# Page-8.net
KiCad netlist of a schematic drawn in Altium Designer
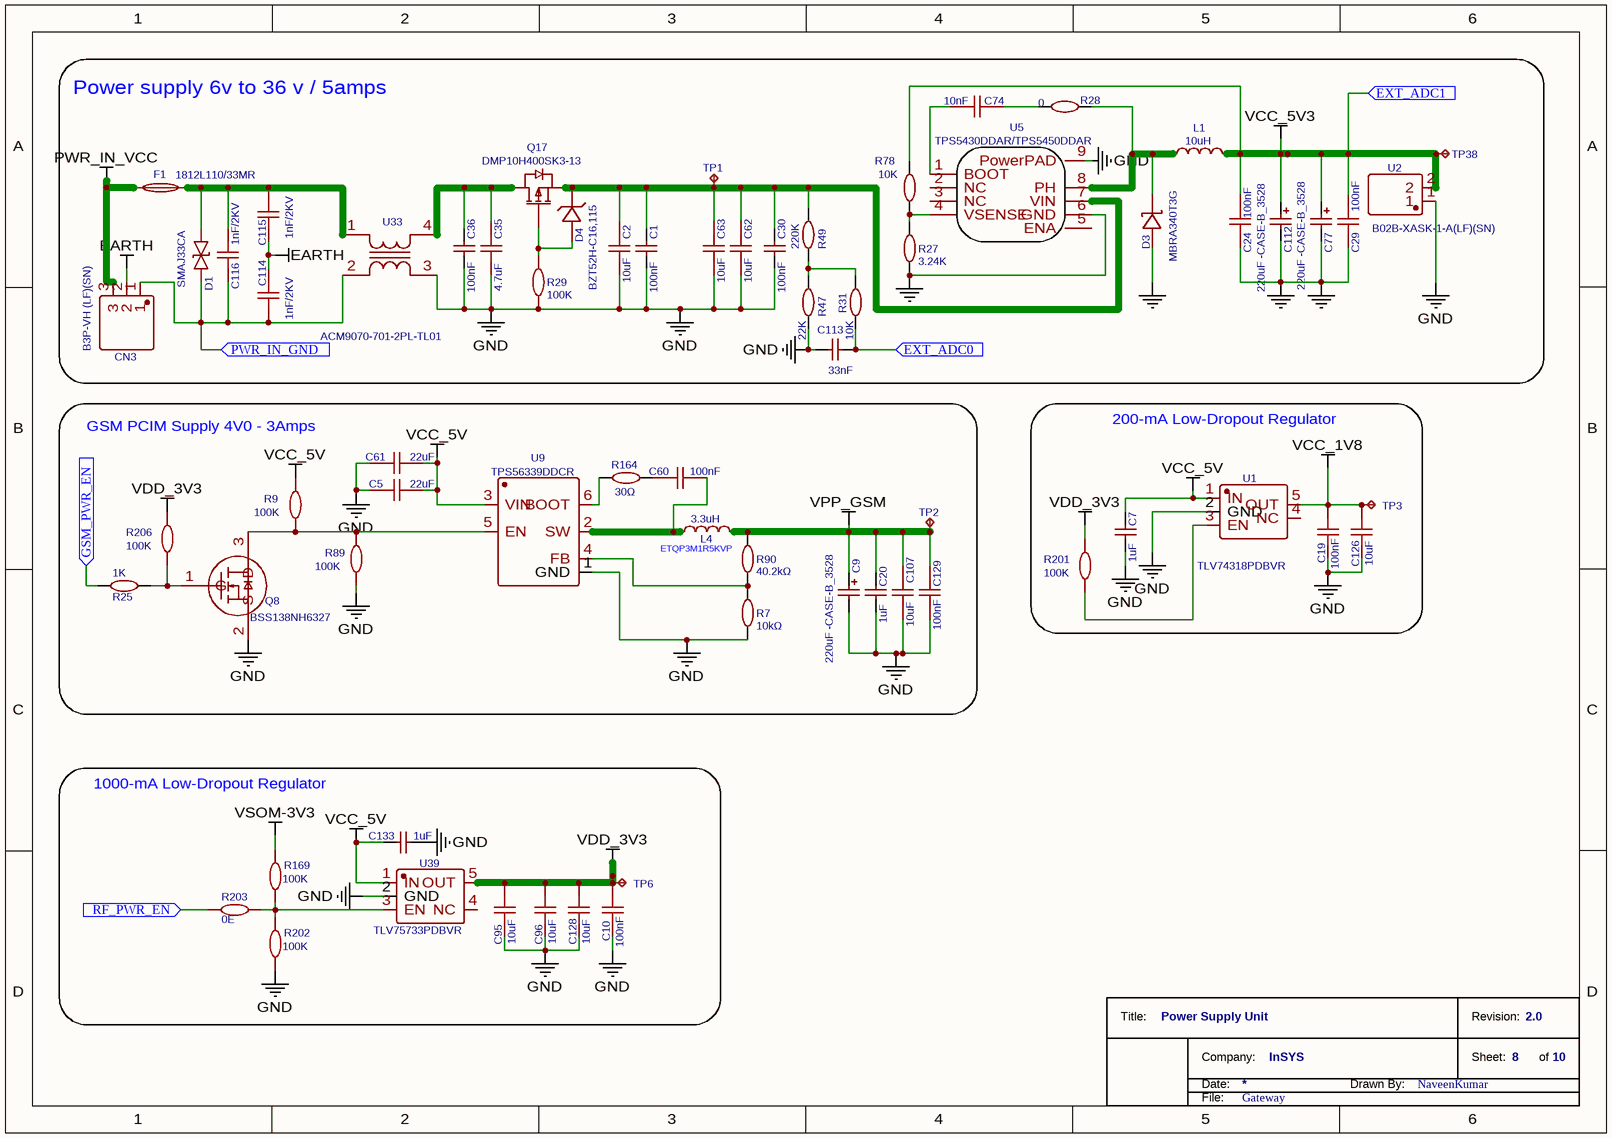
[diagram p0: Page-8.schdoc]

(export (version "E")
  (design (tool "Eeschema 10.0.6"))
  (components
    (comp (ref "*")
      (value "TitleBlock_1")
      (description "TitleBlock  No-2")
      (fields (field (name "DRAWN BY") "*"))
      (libsource (lib "GateWay_AllwinnerV2") (part "TitleBlock_1"))
    )
    (comp (ref "C1")
      (value "100nF")
      (footprint "GWAY_Capacitor_0805")
      (fields
        (field (name "MANUFACTURER PART") "CL21B104KCFNNNE")
        (field (name "MANUFACTURER") "SAMSUNG(三星)")
      )
      (libsource (lib "altium-import") (part "root_1_100nF_"))
    )
    (comp (ref "C2")
      (value "10uF")
      (footprint "GWAY_Capacitor_1206")
      (fields
        (field (name "MANUFACTURER") "SAMSUNG(三星)")
        (field (name "MANUFACTURER PART") "CL31B106KBHNNNE")
      )
      (libsource (lib "altium-import") (part "root_1_10uF_"))
    )
    (comp (ref "C5")
      (value "22uF")
      (footprint "GWAY_Capacitor_0805")
      (fields (field (name "MANUFACTURER") "SAMSUNG") (field (name "MANUFACTURER PART") "CL21A226MQQNNNE"))
      (libsource (lib "altium-import") (part "root_2_22uF_"))
    )
    (comp (ref "C7")
      (value "1uF")
      (footprint "GWAY_Capacitor_0603")
      (fields
        (field (name "MANUFACTURER PART") "CL10B105KA8NNNC")
        (field (name "MANUFACTURER") "SAMSUNG(三星)")
      )
      (libsource (lib "altium-import") (part "root_3_1uF_"))
    )
    (comp (ref "C9")
      (value "220uF -CASE-B_3528")
      (footprint "GWAY_CASE-B")
      (fields (field (name "MANUFACTURER") "PANASONIC") (field (name "MANUFACTURER PART") "6TPE220MAZB"))
      (libsource (lib "altium-import") (part "root_3_220uF -CASE-B_3528_"))
    )
    (comp (ref "C10")
      (value "100nF")
      (footprint "GWAY_Capacitor_0603")
      (fields (field (name "MANUFACTURER") "SAMSUNG") (field (name "MANUFACTURER PART") "CL10B104KB8NNNC"))
      (libsource (lib "") (part "root_1_100nF__1"))
    )
    (comp (ref "C19")
      (value "100nF")
      (footprint "GWAY_Capacitor_0603")
      (fields (field (name "MANUFACTURER") "SAMSUNG") (field (name "MANUFACTURER PART") "CL10B104KB8NNNC"))
      (libsource (lib "") (part "root_1_100nF__1"))
    )
    (comp (ref "C20")
      (value "1uF")
      (footprint "GWAY_Capacitor_0603")
      (fields
        (field (name "MANUFACTURER PART") "CL10B105KA8NNNC")
        (field (name "MANUFACTURER") "SAMSUNG(三星)")
      )
      (libsource (lib "altium-import") (part "root_3_1uF_"))
    )
    (comp (ref "C24")
      (value "100nF")
      (footprint "GWAY_Capacitor_0603")
      (fields (field (name "MANUFACTURER") "SAMSUNG") (field (name "MANUFACTURER PART") "CL10B104KB8NNNC"))
      (libsource (lib "altium-import") (part "root_3_100nF_"))
    )
    (comp (ref "C29")
      (value "100nF")
      (footprint "GWAY_Capacitor_0603")
      (fields (field (name "MANUFACTURER") "SAMSUNG") (field (name "MANUFACTURER PART") "CL10B104KB8NNNC"))
      (libsource (lib "altium-import") (part "root_3_100nF_"))
    )
    (comp (ref "C30")
      (value "100nF")
      (footprint "GWAY_Capacitor_0805")
      (fields
        (field (name "MANUFACTURER PART") "CL21B104KCFNNNE")
        (field (name "MANUFACTURER") "SAMSUNG(三星)")
      )
      (libsource (lib "altium-import") (part "root_1_100nF_"))
    )
    (comp (ref "C35")
      (value "4.7uF")
      (footprint "GWAY_CAP1210")
      (fields
        (field (name "MANUFACTURER") "TAIYO YUDEN(太诱)")
        (field (name "MANUFACTURER PART") "HMK325C7475KN-TE")
        (field (name "CONTRIBUTOR") "LCSC")
      )
      (libsource (lib "altium-import") (part "root_1_4.7uF_"))
    )
    (comp (ref "C36")
      (value "100nF")
      (footprint "GWAY_Capacitor_0805")
      (fields
        (field (name "MANUFACTURER PART") "CL21B104KCFNNNE")
        (field (name "MANUFACTURER") "SAMSUNG(三星)")
      )
      (libsource (lib "altium-import") (part "root_1_100nF_"))
    )
    (comp (ref "C60")
      (value "100nF")
      (footprint "GWAY_Capacitor_0603")
      (fields (field (name "MANUFACTURER") "SAMSUNG") (field (name "MANUFACTURER PART") "CL10B104KB8NNNC"))
      (libsource (lib "altium-import") (part "root_2_100nF_"))
    )
    (comp (ref "C61")
      (value "22uF")
      (footprint "GWAY_Capacitor_0805")
      (fields (field (name "MANUFACTURER") "SAMSUNG") (field (name "MANUFACTURER PART") "CL21A226MQQNNNE"))
      (libsource (lib "altium-import") (part "root_2_22uF_"))
    )
    (comp (ref "C62")
      (value "10uF")
      (footprint "GWAY_Capacitor_1206")
      (fields
        (field (name "MANUFACTURER") "SAMSUNG(三星)")
        (field (name "MANUFACTURER PART") "CL31B106KBHNNNE")
      )
      (libsource (lib "altium-import") (part "root_1_10uF_"))
    )
    (comp (ref "C63")
      (value "10uF")
      (footprint "GWAY_Capacitor_1206")
      (fields
        (field (name "MANUFACTURER") "SAMSUNG(三星)")
        (field (name "MANUFACTURER PART") "CL31B106KBHNNNE")
      )
      (libsource (lib "altium-import") (part "root_1_10uF_"))
    )
    (comp (ref "C74")
      (value "10nF")
      (footprint "GWAY_Capacitor_0603")
      (fields
        (field (name "MANUFACTURER") "Samsung Electro-Mechanics")
        (field (name "MANUFACTURER PART") "CL10B103KB8NFNC")
        (field (name "CONTRIBUTOR") "LCSC")
      )
      (libsource (lib "altium-import") (part "root_1_10nF_"))
    )
    (comp (ref "C77")
      (value "220uF -CASE-B_3528")
      (footprint "GWAY_CASE-B")
      (fields (field (name "MANUFACTURER") "PANASONIC") (field (name "MANUFACTURER PART") "6TPE220MAZB"))
      (libsource (lib "altium-import") (part "root_3_220uF -CASE-B_3528_"))
    )
    (comp (ref "C95")
      (value "10uF")
      (footprint "GWAY_Capacitor_0805")
      (fields
        (field (name "MANUFACTURER") "SAMSUNG(三星)")
        (field (name "MANUFACTURER PART") "CL21B106KOQNNNE")
      )
      (libsource (lib "altium-import") (part "root_1_10uF_"))
    )
    (comp (ref "C96")
      (value "10uF")
      (footprint "GWAY_Capacitor_0805")
      (fields
        (field (name "MANUFACTURER") "SAMSUNG(三星)")
        (field (name "MANUFACTURER PART") "CL21B106KOQNNNE")
      )
      (libsource (lib "altium-import") (part "root_1_10uF_"))
    )
    (comp (ref "C107")
      (value "10uF")
      (footprint "GWAY_Capacitor_0805")
      (fields
        (field (name "MANUFACTURER") "SAMSUNG(三星)")
        (field (name "MANUFACTURER PART") "CL21B106KOQNNNE")
      )
      (libsource (lib "altium-import") (part "root_1_10uF_"))
    )
    (comp (ref "C112")
      (value "220uF -CASE-B_3528")
      (footprint "GWAY_CASE-B")
      (fields (field (name "MANUFACTURER") "PANASONIC") (field (name "MANUFACTURER PART") "6TPE220MAZB"))
      (libsource (lib "altium-import") (part "root_3_220uF -CASE-B_3528_"))
    )
    (comp (ref "C113")
      (value "33nF")
      (footprint "GWAY_Capacitor_0603")
      (fields (field (name "MANUFACTURER PART") "CL10B333KB8NNNC") (field (name "MANUFACTURER") "SAMSUNG"))
      (libsource (lib "altium-import") (part "root_2_33nF_"))
    )
    (comp (ref "C114")
      (value "1nF/2KV")
      (footprint "GWAY_Capacitor_1206")
      (fields
        (field (name "MANUFACTURER") "Walsin Tech Corp")
        (field (name "MANUFACTURER PART") "1206B102K202CT")
        (field (name "CONTRIBUTOR") "LCSC")
      )
      (libsource (lib "altium-import") (part "root_1_1nF/2KV_"))
    )
    (comp (ref "C115")
      (value "1nF/2KV")
      (footprint "GWAY_Capacitor_1206")
      (fields
        (field (name "MANUFACTURER") "Walsin Tech Corp")
        (field (name "MANUFACTURER PART") "1206B102K202CT")
        (field (name "CONTRIBUTOR") "LCSC")
      )
      (libsource (lib "altium-import") (part "root_1_1nF/2KV_"))
    )
    (comp (ref "C116")
      (value "1nF/2KV")
      (footprint "GWAY_Capacitor_1206")
      (fields
        (field (name "MANUFACTURER") "Walsin Tech Corp")
        (field (name "MANUFACTURER PART") "1206B102K202CT")
        (field (name "CONTRIBUTOR") "LCSC")
      )
      (libsource (lib "altium-import") (part "root_1_1nF/2KV_"))
    )
    (comp (ref "C126")
      (value "10uF")
      (footprint "GWAY_Capacitor_0805")
      (fields
        (field (name "MANUFACTURER") "SAMSUNG(三星)")
        (field (name "MANUFACTURER PART") "CL21B106KOQNNNE")
      )
      (libsource (lib "altium-import") (part "root_1_10uF_"))
    )
    (comp (ref "C128")
      (value "10uF")
      (footprint "GWAY_Capacitor_0805")
      (fields
        (field (name "MANUFACTURER") "SAMSUNG(三星)")
        (field (name "MANUFACTURER PART") "CL21B106KOQNNNE")
      )
      (libsource (lib "altium-import") (part "root_1_10uF_"))
    )
    (comp (ref "C129")
      (value "100nF")
      (footprint "GWAY_Capacitor_0603")
      (fields (field (name "MANUFACTURER") "SAMSUNG") (field (name "MANUFACTURER PART") "CL10B104KB8NNNC"))
      (libsource (lib "") (part "root_1_100nF__1"))
    )
    (comp (ref "C133")
      (value "1uF")
      (footprint "GWAY_Capacitor_0603")
      (fields
        (field (name "MANUFACTURER PART") "CL10B105KA8NNNC")
        (field (name "MANUFACTURER") "SAMSUNG(三星)")
      )
      (libsource (lib "altium-import") (part "root_0_1uF_"))
    )
    (comp (ref "CN3")
      (value "B3P-VH (LF)(SN)")
      (footprint "GWAY_B3P-VH-LF-SN")
      (fields (field (name "MANUFACTURER") "JST Sales America") (field (name "CONTRIBUTOR") "LCSC"))
      (libsource (lib "altium-import") (part "root_3_B3P-VH (LF)(SN)_"))
    )
    (comp (ref "D1")
      (value "SMAJ33CA")
      (footprint "GWAY_Diode_SMA_DO214AC")
      (fields (field (name "MANUFACTURER") "Littelfuse") (field (name "CONTRIBUTOR") "LCSC"))
      (libsource (lib "altium-import") (part "root_1_SMAJ33CA_"))
    )
    (comp (ref "D3")
      (value "MBRA340T3G")
      (footprint "GWAY_Diode_SMA_DO214AC")
      (fields (field (name "MANUFACTURER") "ON"))
      (libsource (lib "altium-import") (part "root_1_MBRA340T3G_"))
    )
    (comp (ref "D4")
      (value "BZT52H-C16,115")
      (footprint "GWAY_SOD123F")
      (fields (field (name "MANUFACTURER") "Nexperia(安世)") (field (name "CONTRIBUTOR") "LCSC"))
      (libsource (lib "altium-import") (part "root_3_BZT52H-C16,115_"))
    )
    (comp (ref "F1")
      (value "1812L110/33MR")
      (footprint "GWAY_FUSE1812L110/33MR")
      (fields (field (name "MANUFACTURER") "Littelfuse") (field (name "CONTRIBUTOR") "LCSC"))
      (libsource (lib "altium-import") (part "root_0_1812L110/33MR_"))
    )
    (comp (ref "L1")
      (value "10uH")
      (footprint "GWAY_ETQP5M100YFC")
      (fields
        (field (name "MANUFACTURER") "PANASONIC")
        (field (name "MANUFACTURER PART") "ETQP5M100YFC")
        (field (name "CONTRIBUTOR") "LCSC")
      )
      (libsource (lib "altium-import") (part "root_0_10uH_"))
    )
    (comp (ref "L4")
      (value "3.3uH")
      (footprint "GWAY_ETQ-P3M_KVP")
      (fields (field (name "MANUFACTURER PART") "TDK") (field (name "MANUFACTURER") "ETQP3M3R3KVP"))
      (libsource (lib "altium-import") (part "root_0_3.3uH_"))
    )
    (comp (ref "Q8")
      (value "BSS138NH6327")
      (footprint "GWAY_SOT23-3PIN")
      (fields (field (name "MANUFACTURER") "Infineon(英飞凌)") (field (name "CONTRIBUTOR") "LCSC"))
      (libsource (lib "GateWay_AllwinnerV2") (part "BSS138NH6327"))
    )
    (comp (ref "Q17")
      (value "DMP10H400SK3-13")
      (footprint "GWAY_P-CH MOSFET_DMP10H400SK313")
      (fields (field (name "MANUFACTURER") "DIODES(美台)") (field (name "CONTRIBUTOR") "LCSC"))
      (libsource (lib "altium-import") (part "root_1_DMP10H400SK3-13_"))
    )
    (comp (ref "R7")
      (value "10kΩ")
      (footprint "GWAY_Resistor_0603")
      (fields (field (name "MANUFACTURER") "YAGEO(国巨)"))
      (libsource (lib "altium-import") (part "root_1_10kΩ_"))
    )
    (comp (ref "R9")
      (value "100K")
      (footprint "GWAY_Resistor_0603")
      (fields
        (field (name "MANUFACTURER") "YAGEO")
        (field (name "MANUFACTURER PART") "RC0603FR-07100KL")
        (field (name "CONTRIBUTOR") "LCSC")
      )
      (libsource (lib "altium-import") (part "root_1_100K_"))
    )
    (comp (ref "R25")
      (value "1K")
      (footprint "GWAY_Resistor_0603")
      (fields (field (name "MANUFACTURER PART") "RC0603FR-071KL") (field (name "MANUFACTURER") "YAGEO"))
      (libsource (lib "altium-import") (part "root_2_1K_"))
    )
    (comp (ref "R27")
      (value "3.24K")
      (footprint "GWAY_Resistor_0603")
      (fields (field (name "MANUFACTURER") "YAGEO") (field (name "MANUFACTURER PART") "RC0603FR-073KL"))
      (libsource (lib "altium-import") (part "root_1_3.24K_"))
    )
    (comp (ref "R28")
      (value "0")
      (footprint "GWAY_Resistor_0603")
      (fields (field (name "MANUFACTURER") "YAGEO") (field (name "MANUFACTURER PART") "RC0603FR-070RL"))
      (libsource (lib "altium-import") (part "root_0_0_"))
    )
    (comp (ref "R29")
      (value "100K")
      (footprint "GWAY_Resistor_0603")
      (fields
        (field (name "MANUFACTURER") "YAGEO")
        (field (name "MANUFACTURER PART") "RC0603FR-07100KL")
        (field (name "CONTRIBUTOR") "LCSC")
      )
      (libsource (lib "altium-import") (part "root_1_100K_"))
    )
    (comp (ref "R31")
      (value "10K")
      (footprint "GWAY_Resistor_0603")
      (fields (field (name "MANUFACTURER") "YAGEO") (field (name "MANUFACTURER PART") "RC0603JR-0710KL"))
      (libsource (lib "altium-import") (part "root_3_10K_"))
    )
    (comp (ref "R47")
      (value "22K")
      (footprint "GWAY_Resistor_0805")
      (fields (field (name "MANUFACTURER") "YAGEO") (field (name "MANUFACTURER PART") "RC0805JR-0722KL"))
      (libsource (lib "altium-import") (part "root_1_22K_"))
    )
    (comp (ref "R49")
      (value "220K")
      (footprint "GWAY_Resistor_0805")
      (fields (field (name "MANUFACTURER") "YAGEO") (field (name "MANUFACTURER PART") "RC0805FR-07220KL"))
      (libsource (lib "altium-import") (part "root_1_220K_"))
    )
    (comp (ref "R78")
      (value "10K")
      (footprint "GWAY_Resistor_0603")
      (fields (field (name "MANUFACTURER") "YAGEO") (field (name "MANUFACTURER PART") "RC0603JR-0710KL"))
      (libsource (lib "altium-import") (part "root_3_10K_"))
    )
    (comp (ref "R89")
      (value "100K")
      (footprint "GWAY_Resistor_0603")
      (fields
        (field (name "MANUFACTURER") "YAGEO")
        (field (name "MANUFACTURER PART") "RC0603FR-07100KL")
        (field (name "CONTRIBUTOR") "LCSC")
      )
      (libsource (lib "altium-import") (part "root_1_100K_"))
    )
    (comp (ref "R90")
      (value "40.2kΩ")
      (footprint "GWAY_Resistor_0603")
      (fields (field (name "MANUFACTURER") "YAGEO(国巨)"))
      (libsource (lib "altium-import") (part "root_1_40.2kΩ_"))
    )
    (comp (ref "R164")
      (value "30Ω")
      (footprint "GWAY_Resistor_0603")
      (fields (field (name "MANUFACTURER") "YAGEO(国巨)"))
      (libsource (lib "altium-import") (part "root_0_30Ω_"))
    )
    (comp (ref "R169")
      (value "100K")
      (footprint "GWAY_Resistor_0603")
      (fields
        (field (name "MANUFACTURER") "YAGEO")
        (field (name "MANUFACTURER PART") "RC0603FR-07100KL")
        (field (name "CONTRIBUTOR") "LCSC")
      )
      (libsource (lib "altium-import") (part "root_1_100K_"))
    )
    (comp (ref "R201")
      (value "100K")
      (footprint "GWAY_Resistor_0603")
      (fields
        (field (name "MANUFACTURER") "YAGEO")
        (field (name "MANUFACTURER PART") "RC0603FR-07100KL")
        (field (name "CONTRIBUTOR") "LCSC")
      )
      (libsource (lib "altium-import") (part "root_1_100K_"))
    )
    (comp (ref "R202")
      (value "100K")
      (footprint "GWAY_Resistor_0603")
      (fields
        (field (name "MANUFACTURER") "YAGEO")
        (field (name "MANUFACTURER PART") "RC0603FR-07100KL")
        (field (name "CONTRIBUTOR") "LCSC")
      )
      (libsource (lib "altium-import") (part "root_1_100K_"))
    )
    (comp (ref "R203")
      (value "0E")
      (footprint "GWAY_Resistor_0603")
      (fields
        (field (name "MANUFACTURER") "YAGEO")
        (field (name "MANUFACTURER PART") "RC0603FR-07100KL")
        (field (name "CONTRIBUTOR") "LCSC")
      )
      (libsource (lib "altium-import") (part "root_2_100K_"))
    )
    (comp (ref "R206")
      (value "100K")
      (footprint "GWAY_Resistor_0603")
      (fields
        (field (name "MANUFACTURER") "YAGEO")
        (field (name "MANUFACTURER PART") "RC0603FR-07100KL")
        (field (name "CONTRIBUTOR") "LCSC")
      )
      (libsource (lib "altium-import") (part "root_1_100K_"))
    )
    (comp (ref "TP1")
      (value "TP-052-TJ")
      (footprint "GWAY_TESTPOINT1")
      (fields (field (name "MANUFACTURER PART") "?"))
      (libsource (lib "altium-import") (part "root_0_TP-052-TJ_"))
    )
    (comp (ref "TP2")
      (value "TP-052-TJ")
      (footprint "GWAY_TESTPOINT1")
      (fields (field (name "MANUFACTURER PART") "?"))
      (libsource (lib "altium-import") (part "root_0_TP-052-TJ_"))
    )
    (comp (ref "TP3")
      (value "TP-052-TJ")
      (footprint "GWAY_TESTPOINT1")
      (fields (field (name "MANUFACTURER PART") "?"))
      (libsource (lib "altium-import") (part "root_3_TP-052-TJ_"))
    )
    (comp (ref "TP6")
      (value "TP-052-TJ")
      (footprint "GWAY_TESTPOINT1")
      (fields (field (name "MANUFACTURER PART") "?"))
      (libsource (lib "altium-import") (part "root_3_TP-052-TJ_"))
    )
    (comp (ref "TP38")
      (value "TP-052-TJ")
      (footprint "GWAY_TESTPOINT1")
      (fields (field (name "MANUFACTURER PART") "?"))
      (libsource (lib "altium-import") (part "root_3_TP-052-TJ_"))
    )
    (comp (ref "U1")
      (value "TLV74318PDBVR")
      (footprint "GWAY_SOT23-5PIN")
      (fields (field (name "MANUFACTURER") "Texas Instruments") (field (name "CONTRIBUTOR") "LCSC"))
      (libsource (lib "altium-import") (part "root_0_TLV74318PDBVR_"))
    )
    (comp (ref "U2")
      (value "B02B-XASK-1-A(LF)(SN)")
      (footprint "GWAY_B2P-VH-LF-SN")
      (fields (field (name "MANUFACTURER") "JST") (field (name "CONTRIBUTOR") "LCSC"))
      (libsource (lib "altium-import") (part "root_2_B02B-XASK-1-A(LF)(SN)_"))
    )
    (comp (ref "U5")
      (value "TPS5430DDAR/TPS5450DDAR")
      (footprint "GWAY_SOIC8_POWERPAD")
      (fields (field (name "MANUFACTURER") "TI") (field (name "MANUFACTURER PART") "TPS5430DDAR"))
      (libsource (lib "altium-import") (part "root_0_TPS5430DDAR/TPS5450DDAR_"))
    )
    (comp (ref "U9")
      (value "TPS56339DDCR")
      (footprint "GWAY_TSOT23-6PIN")
      (fields (field (name "MANUFACTURER") "TI") (field (name "CONTRIBUTOR") "jinyoung00"))
      (libsource (lib "altium-import") (part "root_0_TPS56339DDCR_"))
    )
    (comp (ref "U33")
      (value "ACM9070-701-2PL-TL01")
      (footprint "GWay_ACM9070-701-2PL-TL01")
      (fields (field (name "MANUFACTURER") "TDK") (field (name "CONTRIBUTOR") "LCSC"))
      (libsource (lib "altium-import") (part "root_0_ACM9070-701-2PL-TL01_"))
    )
    (comp (ref "U39")
      (value "TLV75733PDBVR")
      (footprint "GWAY_SOT23-5PIN")
      (fields (field (name "MANUFACTURER") "Texas Instruments") (field (name "CONTRIBUTOR") "LCSC"))
      (libsource (lib "altium-import") (part "root_0_TLV75733PDBVR_"))
    )
  )
  (nets
    (net (code "1") (name "/EXT_ADC0") (class "Default")
      (node (ref "C113") (pin "1") (pinfunction "1_1") (pintype "passive"))
      (node (ref "R31") (pin "2") (pinfunction "2_2") (pintype "passive"))
    )
    (net (code "2") (name "/GSM_PWR_EN") (class "Default")
      (node (ref "R25") (pin "2") (pinfunction "2_2") (pintype "passive"))
    )
    (net (code "3") (name "/PWR_IN_GND") (class "Default")
      (node (ref "C114") (pin "2") (pinfunction "2_2") (pintype "passive"))
      (node (ref "C116") (pin "2") (pinfunction "2_2") (pintype "passive"))
      (node (ref "CN3") (pin "1") (pinfunction "1_1") (pintype "passive"))
      (node (ref "D1") (pin "1") (pinfunction "K_1") (pintype "passive"))
      (node (ref "U33") (pin "2") (pinfunction "2_2") (pintype "passive"))
    )
    (net (code "4") (name "/RF_PWR_EN") (class "Default")
      (node (ref "R203") (pin "2") (pinfunction "2_2") (pintype "passive"))
    )
    (net (code "5") (name "EARTH") (class "Default")
      (node (ref "C114") (pin "1") (pinfunction "1_1") (pintype "passive"))
      (node (ref "C115") (pin "2") (pinfunction "2_2") (pintype "passive"))
      (node (ref "CN3") (pin "2") (pinfunction "2_2") (pintype "passive"))
    )
    (net (code "6") (name "GND") (class "Default")
      (node (ref "C1") (pin "1") (pinfunction "1_1") (pintype "passive"))
      (node (ref "C10") (pin "1") (pinfunction "1_1") (pintype "passive"))
      (node (ref "C107") (pin "1") (pinfunction "1_1") (pintype "passive"))
      (node (ref "C112") (pin "2") (pinfunction "2_2") (pintype "passive"))
      (node (ref "C113") (pin "2") (pinfunction "2_2") (pintype "passive"))
      (node (ref "C126") (pin "1") (pinfunction "1_1") (pintype "passive"))
      (node (ref "C128") (pin "1") (pinfunction "1_1") (pintype "passive"))
      (node (ref "C129") (pin "1") (pinfunction "1_1") (pintype "passive"))
      (node (ref "C133") (pin "2") (pinfunction "2_2") (pintype "passive"))
      (node (ref "C19") (pin "1") (pinfunction "1_1") (pintype "passive"))
      (node (ref "C2") (pin "1") (pinfunction "1_1") (pintype "passive"))
      (node (ref "C20") (pin "2") (pinfunction "2_2") (pintype "passive"))
      (node (ref "C24") (pin "2") (pinfunction "2_2") (pintype "passive"))
      (node (ref "C29") (pin "2") (pinfunction "2_2") (pintype "passive"))
      (node (ref "C30") (pin "1") (pinfunction "1_1") (pintype "passive"))
      (node (ref "C35") (pin "1") (pinfunction "1_1") (pintype "passive"))
      (node (ref "C36") (pin "1") (pinfunction "1_1") (pintype "passive"))
      (node (ref "C5") (pin "2") (pinfunction "2_2") (pintype "passive"))
      (node (ref "C61") (pin "2") (pinfunction "2_2") (pintype "passive"))
      (node (ref "C62") (pin "1") (pinfunction "1_1") (pintype "passive"))
      (node (ref "C63") (pin "1") (pinfunction "1_1") (pintype "passive"))
      (node (ref "C7") (pin "2") (pinfunction "2_2") (pintype "passive"))
      (node (ref "C77") (pin "2") (pinfunction "2_2") (pintype "passive"))
      (node (ref "C9") (pin "2") (pinfunction "2_2") (pintype "passive"))
      (node (ref "C95") (pin "1") (pinfunction "1_1") (pintype "passive"))
      (node (ref "C96") (pin "1") (pinfunction "1_1") (pintype "passive"))
      (node (ref "D3") (pin "1") (pinfunction "A_1") (pintype "passive"))
      (node (ref "Q8") (pin "2") (pinfunction "S_2") (pintype "passive"))
      (node (ref "R202") (pin "1") (pinfunction "1_1") (pintype "passive"))
      (node (ref "R27") (pin "1") (pinfunction "1_1") (pintype "passive"))
      (node (ref "R29") (pin "1") (pinfunction "1_1") (pintype "passive"))
      (node (ref "R47") (pin "1") (pinfunction "1_1") (pintype "passive"))
      (node (ref "R7") (pin "1") (pinfunction "1_1") (pintype "passive"))
      (node (ref "R89") (pin "1") (pinfunction "1_1") (pintype "passive"))
      (node (ref "U1") (pin "2") (pinfunction "GND_2") (pintype "passive"))
      (node (ref "U2") (pin "1") (pinfunction "1_1") (pintype "passive"))
      (node (ref "U33") (pin "3") (pinfunction "3_3") (pintype "passive"))
      (node (ref "U39") (pin "2") (pinfunction "GND_2") (pintype "passive"))
      (node (ref "U5") (pin "6") (pinfunction "GND_6") (pintype "passive"))
      (node (ref "U5") (pin "9") (pinfunction "PowerPAD_9") (pintype "passive"))
      (node (ref "U9") (pin "1") (pinfunction "GND_1") (pintype "passive"))
    )
    (net (code "7") (name "Net-(C60-Pad2)") (class "Default")
      (node (ref "C60") (pin "2") (pinfunction "2_2") (pintype "passive"))
      (node (ref "R164") (pin "2") (pinfunction "2_2") (pintype "passive"))
    )
    (net (code "8") (name "Net-(C74-Pad1)") (class "Default")
      (node (ref "C74") (pin "1") (pinfunction "1_1") (pintype "passive"))
      (node (ref "R28") (pin "1") (pinfunction "1_1") (pintype "passive"))
    )
    (net (code "9") (name "Net-(D1-A)") (class "Default")
      (node (ref "C115") (pin "1") (pinfunction "1_1") (pintype "passive"))
      (node (ref "C116") (pin "1") (pinfunction "1_1") (pintype "passive"))
      (node (ref "D1") (pin "2") (pinfunction "A_2") (pintype "passive"))
      (node (ref "F1") (pin "2") (pinfunction "2_2") (pintype "passive"))
      (node (ref "U33") (pin "1") (pinfunction "1_1") (pintype "passive"))
    )
    (net (code "10") (name "Net-(D3-K)") (class "Default")
      (node (ref "D3") (pin "2") (pinfunction "K_2") (pintype "passive"))
      (node (ref "L1") (pin "1") (pinfunction "1_1") (pintype "passive"))
      (node (ref "R28") (pin "2") (pinfunction "2_2") (pintype "passive"))
      (node (ref "U5") (pin "8") (pinfunction "PH_8") (pintype "passive"))
    )
    (net (code "11") (name "Net-(D4-A)") (class "Default")
      (node (ref "D4") (pin "2") (pinfunction "A_2") (pintype "passive"))
      (node (ref "Q17") (pin "1") (pinfunction "G_1") (pintype "passive"))
      (node (ref "R29") (pin "2") (pinfunction "2_2") (pintype "passive"))
    )
    (net (code "12") (name "Net-(D4-K)") (class "Default")
      (node (ref "C1") (pin "2") (pinfunction "2_2") (pintype "passive"))
      (node (ref "C2") (pin "2") (pinfunction "2_2") (pintype "passive"))
      (node (ref "C30") (pin "2") (pinfunction "2_2") (pintype "passive"))
      (node (ref "C62") (pin "2") (pinfunction "2_2") (pintype "passive"))
      (node (ref "C63") (pin "2") (pinfunction "2_2") (pintype "passive"))
      (node (ref "D4") (pin "1") (pinfunction "K_1") (pintype "passive"))
      (node (ref "Q17") (pin "3") (pinfunction "S_3") (pintype "passive"))
      (node (ref "R49") (pin "2") (pinfunction "2_2") (pintype "passive"))
      (node (ref "TP1") (pin "1") (pinfunction "1_1") (pintype "passive"))
      (node (ref "U5") (pin "7") (pinfunction "VIN_7") (pintype "passive"))
    )
    (net (code "13") (name "Net-(Q8-D)") (class "Default")
      (node (ref "Q8") (pin "3") (pinfunction "D_3") (pintype "passive"))
      (node (ref "R89") (pin "2") (pinfunction "2_2") (pintype "passive"))
      (node (ref "R9") (pin "1") (pinfunction "1_1") (pintype "passive"))
      (node (ref "U9") (pin "5") (pinfunction "EN_5") (pintype "passive"))
    )
    (net (code "14") (name "Net-(Q8-G)") (class "Default")
      (node (ref "Q8") (pin "1") (pinfunction "G_1") (pintype "passive"))
      (node (ref "R206") (pin "1") (pinfunction "1_1") (pintype "passive"))
      (node (ref "R25") (pin "1") (pinfunction "1_1") (pintype "passive"))
    )
    (net (code "15") (name "Net-(Q17-D)") (class "Default")
      (node (ref "C35") (pin "2") (pinfunction "2_2") (pintype "passive"))
      (node (ref "C36") (pin "2") (pinfunction "2_2") (pintype "passive"))
      (node (ref "Q17") (pin "2") (pinfunction "D_2") (pintype "passive"))
      (node (ref "U33") (pin "4") (pinfunction "4_4") (pintype "passive"))
    )
    (net (code "16") (name "Net-(R31-Pad1)") (class "Default")
      (node (ref "R31") (pin "1") (pinfunction "1_1") (pintype "passive"))
      (node (ref "R47") (pin "2") (pinfunction "2_2") (pintype "passive"))
      (node (ref "R49") (pin "1") (pinfunction "1_1") (pintype "passive"))
    )
    (net (code "17") (name "Net-(U1-EN)") (class "Default")
      (node (ref "R201") (pin "1") (pinfunction "1_1") (pintype "passive"))
      (node (ref "U1") (pin "3") (pinfunction "EN_3") (pintype "passive"))
    )
    (net (code "18") (name "Net-(U5-BOOT)") (class "Default")
      (node (ref "C74") (pin "2") (pinfunction "2_2") (pintype "passive"))
      (node (ref "U5") (pin "1") (pinfunction "BOOT_1") (pintype "passive"))
    )
    (net (code "19") (name "Net-(U5-VSENSE)") (class "Default")
      (node (ref "R27") (pin "2") (pinfunction "2_2") (pintype "passive"))
      (node (ref "R78") (pin "2") (pinfunction "2_2") (pintype "passive"))
      (node (ref "U5") (pin "4") (pinfunction "VSENSE_4") (pintype "passive"))
    )
    (net (code "20") (name "Net-(U9-BOOT)") (class "Default")
      (node (ref "R164") (pin "1") (pinfunction "1_1") (pintype "passive"))
      (node (ref "U9") (pin "6") (pinfunction "BOOT_6") (pintype "passive"))
    )
    (net (code "21") (name "Net-(U9-FB)") (class "Default")
      (node (ref "R7") (pin "2") (pinfunction "2_2") (pintype "passive"))
      (node (ref "R90") (pin "1") (pinfunction "1_1") (pintype "passive"))
      (node (ref "U9") (pin "4") (pinfunction "FB_4") (pintype "passive"))
    )
    (net (code "22") (name "Net-(U9-SW)") (class "Default")
      (node (ref "C60") (pin "1") (pinfunction "1_1") (pintype "passive"))
      (node (ref "L4") (pin "1") (pinfunction "1_1") (pintype "passive"))
      (node (ref "U9") (pin "2") (pinfunction "SW_2") (pintype "passive"))
    )
    (net (code "23") (name "Net-(U39-EN)") (class "Default")
      (node (ref "R169") (pin "1") (pinfunction "1_1") (pintype "passive"))
      (node (ref "R202") (pin "2") (pinfunction "2_2") (pintype "passive"))
      (node (ref "R203") (pin "1") (pinfunction "1_1") (pintype "passive"))
      (node (ref "U39") (pin "3") (pinfunction "EN_3") (pintype "passive"))
    )
    (net (code "24") (name "PWR_IN_VCC") (class "Default")
      (node (ref "CN3") (pin "3") (pinfunction "3_3") (pintype "passive"))
      (node (ref "F1") (pin "1") (pinfunction "1_1") (pintype "passive"))
    )
    (net (code "25") (name "VCC_1V8") (class "Default")
      (node (ref "C126") (pin "2") (pinfunction "2_2") (pintype "passive"))
      (node (ref "C19") (pin "2") (pinfunction "2_2") (pintype "passive"))
      (node (ref "TP3") (pin "1") (pinfunction "1_1") (pintype "passive"))
      (node (ref "U1") (pin "5") (pinfunction "OUT_5") (pintype "passive"))
    )
    (net (code "26") (name "VCC_5V") (class "Default")
      (node (ref "C133") (pin "1") (pinfunction "1_1") (pintype "passive"))
      (node (ref "C5") (pin "1") (pinfunction "1_1") (pintype "passive"))
      (node (ref "C61") (pin "1") (pinfunction "1_1") (pintype "passive"))
      (node (ref "C7") (pin "1") (pinfunction "1_1") (pintype "passive"))
      (node (ref "R9") (pin "2") (pinfunction "2_2") (pintype "passive"))
      (node (ref "U1") (pin "1") (pinfunction "IN_1") (pintype "passive"))
      (node (ref "U39") (pin "1") (pinfunction "IN_1") (pintype "passive"))
      (node (ref "U9") (pin "3") (pinfunction "VIN_3") (pintype "passive"))
    )
    (net (code "27") (name "VCC_5V3") (class "Default")
      (node (ref "C112") (pin "1") (pinfunction "1_1") (pintype "passive"))
      (node (ref "C24") (pin "1") (pinfunction "1_1") (pintype "passive"))
      (node (ref "C29") (pin "1") (pinfunction "1_1") (pintype "passive"))
      (node (ref "C77") (pin "1") (pinfunction "1_1") (pintype "passive"))
      (node (ref "L1") (pin "2") (pinfunction "2_2") (pintype "passive"))
      (node (ref "R78") (pin "1") (pinfunction "1_1") (pintype "passive"))
      (node (ref "TP38") (pin "1") (pinfunction "1_1") (pintype "passive"))
      (node (ref "U2") (pin "2") (pinfunction "2_2") (pintype "passive"))
    )
    (net (code "28") (name "VDD_3V3") (class "Default")
      (node (ref "C10") (pin "2") (pinfunction "2_2") (pintype "passive"))
      (node (ref "C128") (pin "2") (pinfunction "2_2") (pintype "passive"))
      (node (ref "C95") (pin "2") (pinfunction "2_2") (pintype "passive"))
      (node (ref "C96") (pin "2") (pinfunction "2_2") (pintype "passive"))
      (node (ref "R201") (pin "2") (pinfunction "2_2") (pintype "passive"))
      (node (ref "R206") (pin "2") (pinfunction "2_2") (pintype "passive"))
      (node (ref "TP6") (pin "1") (pinfunction "1_1") (pintype "passive"))
      (node (ref "U39") (pin "5") (pinfunction "OUT_5") (pintype "passive"))
    )
    (net (code "29") (name "VPP_GSM") (class "Default")
      (node (ref "C107") (pin "2") (pinfunction "2_2") (pintype "passive"))
      (node (ref "C129") (pin "2") (pinfunction "2_2") (pintype "passive"))
      (node (ref "C20") (pin "1") (pinfunction "1_1") (pintype "passive"))
      (node (ref "C9") (pin "1") (pinfunction "1_1") (pintype "passive"))
      (node (ref "L4") (pin "2") (pinfunction "2_2") (pintype "passive"))
      (node (ref "R90") (pin "2") (pinfunction "2_2") (pintype "passive"))
      (node (ref "TP2") (pin "1") (pinfunction "1_1") (pintype "passive"))
    )
    (net (code "30") (name "VSOM-3V3") (class "Default")
      (node (ref "R169") (pin "2") (pinfunction "2_2") (pintype "passive"))
    )
    (net (code "31") (name "unconnected-(U1-NC-Pad4)") (class "Default")
      (node (ref "U1") (pin "4") (pinfunction "NC_4") (pintype "passive"))
    )
    (net (code "32") (name "unconnected-(U5-ENA-Pad5)") (class "Default")
      (node (ref "U5") (pin "5") (pinfunction "ENA_5") (pintype "passive"))
    )
    (net (code "33") (name "unconnected-(U5-NC-Pad2)") (class "Default")
      (node (ref "U5") (pin "2") (pinfunction "NC_2") (pintype "passive"))
    )
    (net (code "34") (name "unconnected-(U5-NC-Pad3)") (class "Default")
      (node (ref "U5") (pin "3") (pinfunction "NC_3") (pintype "passive"))
    )
    (net (code "35") (name "unconnected-(U39-NC-Pad4)") (class "Default")
      (node (ref "U39") (pin "4") (pinfunction "NC_4") (pintype "passive"))
    )
  )
)
